# ProDoc_Schematic1.net
KiCad netlist of a schematic drawn in EasyEDA Pro
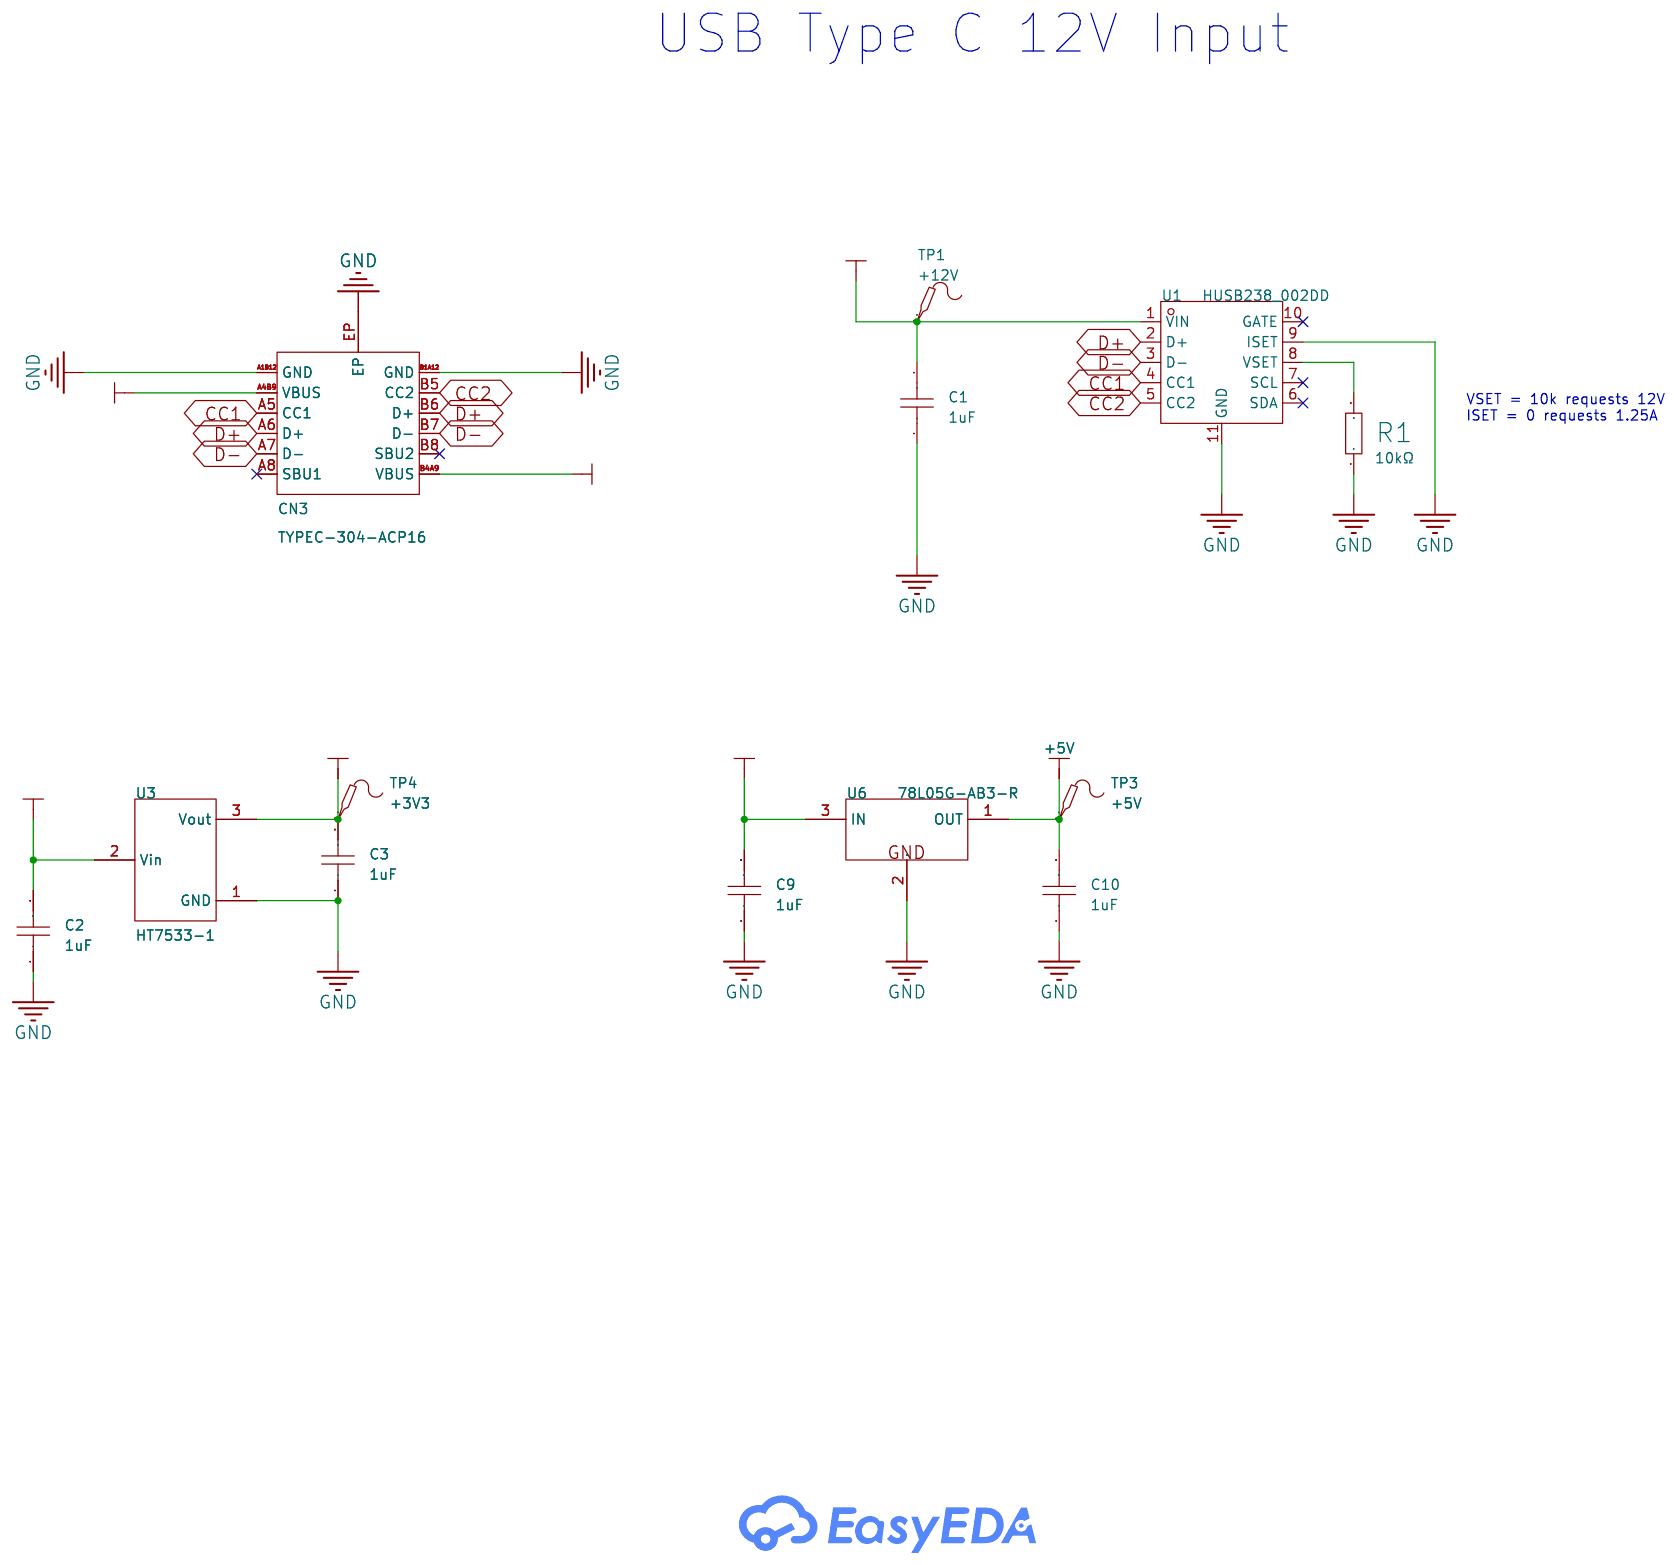
[diagram p0: P1]
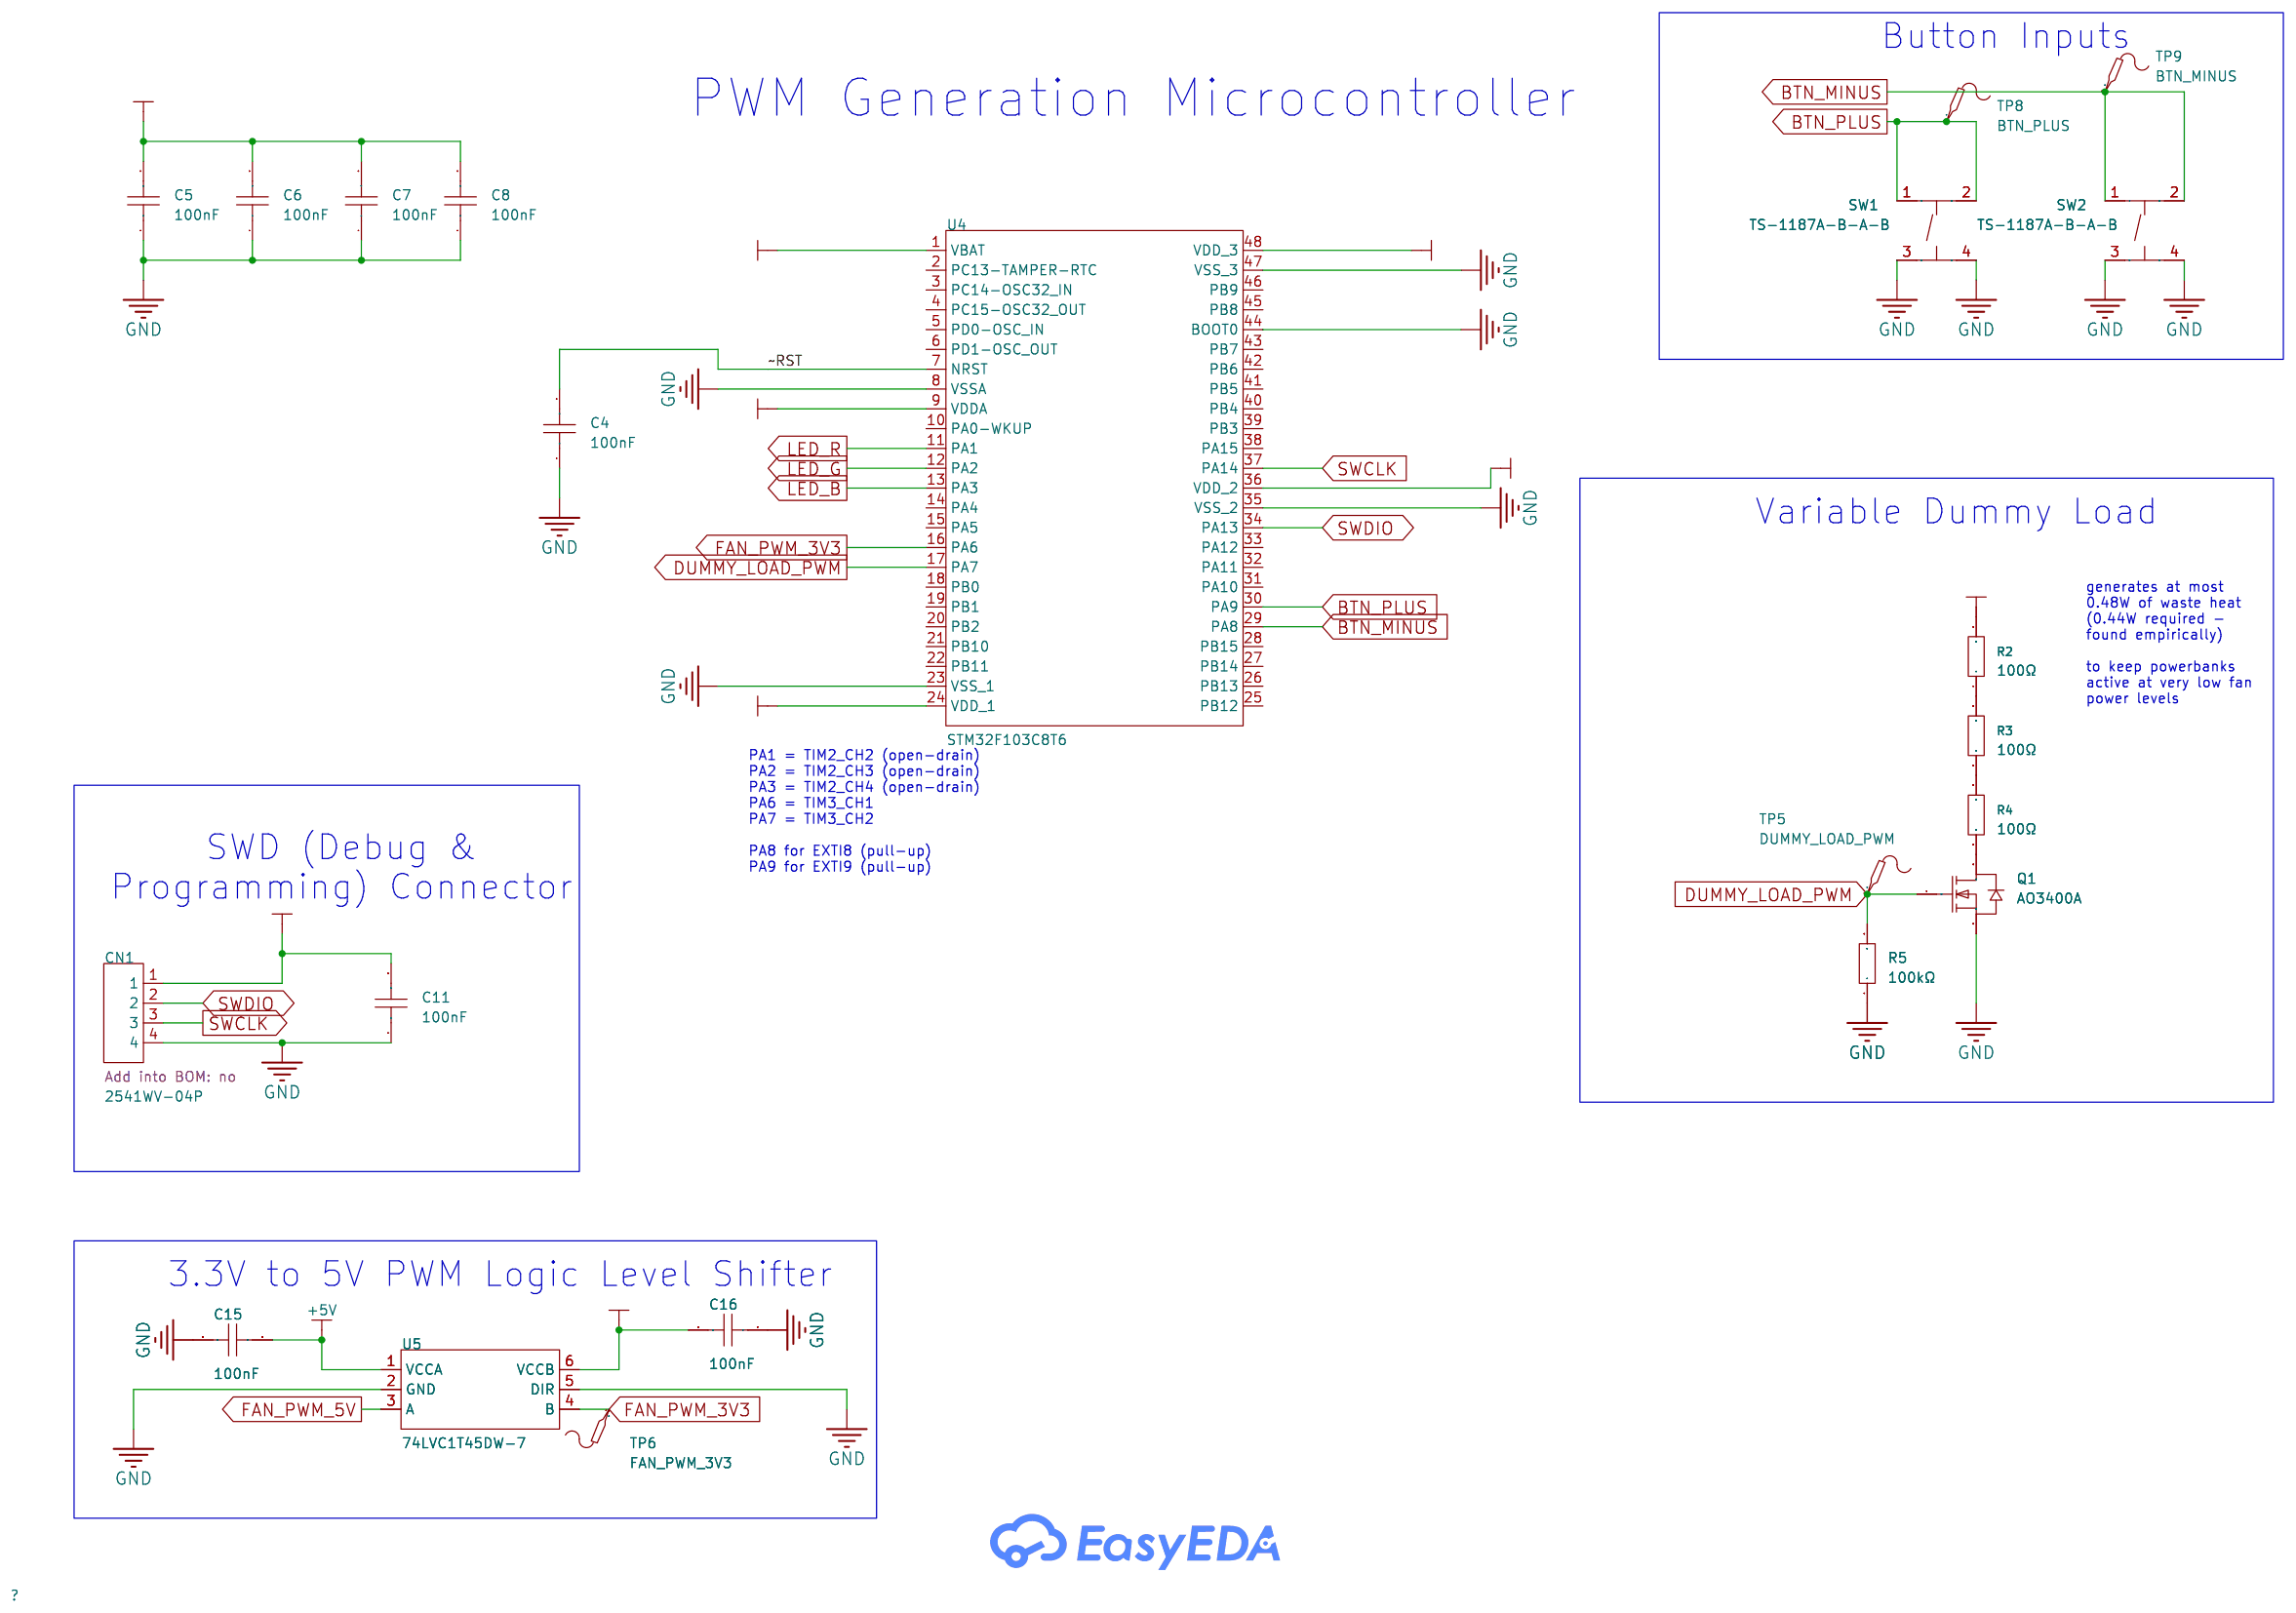
[diagram p1: P2]
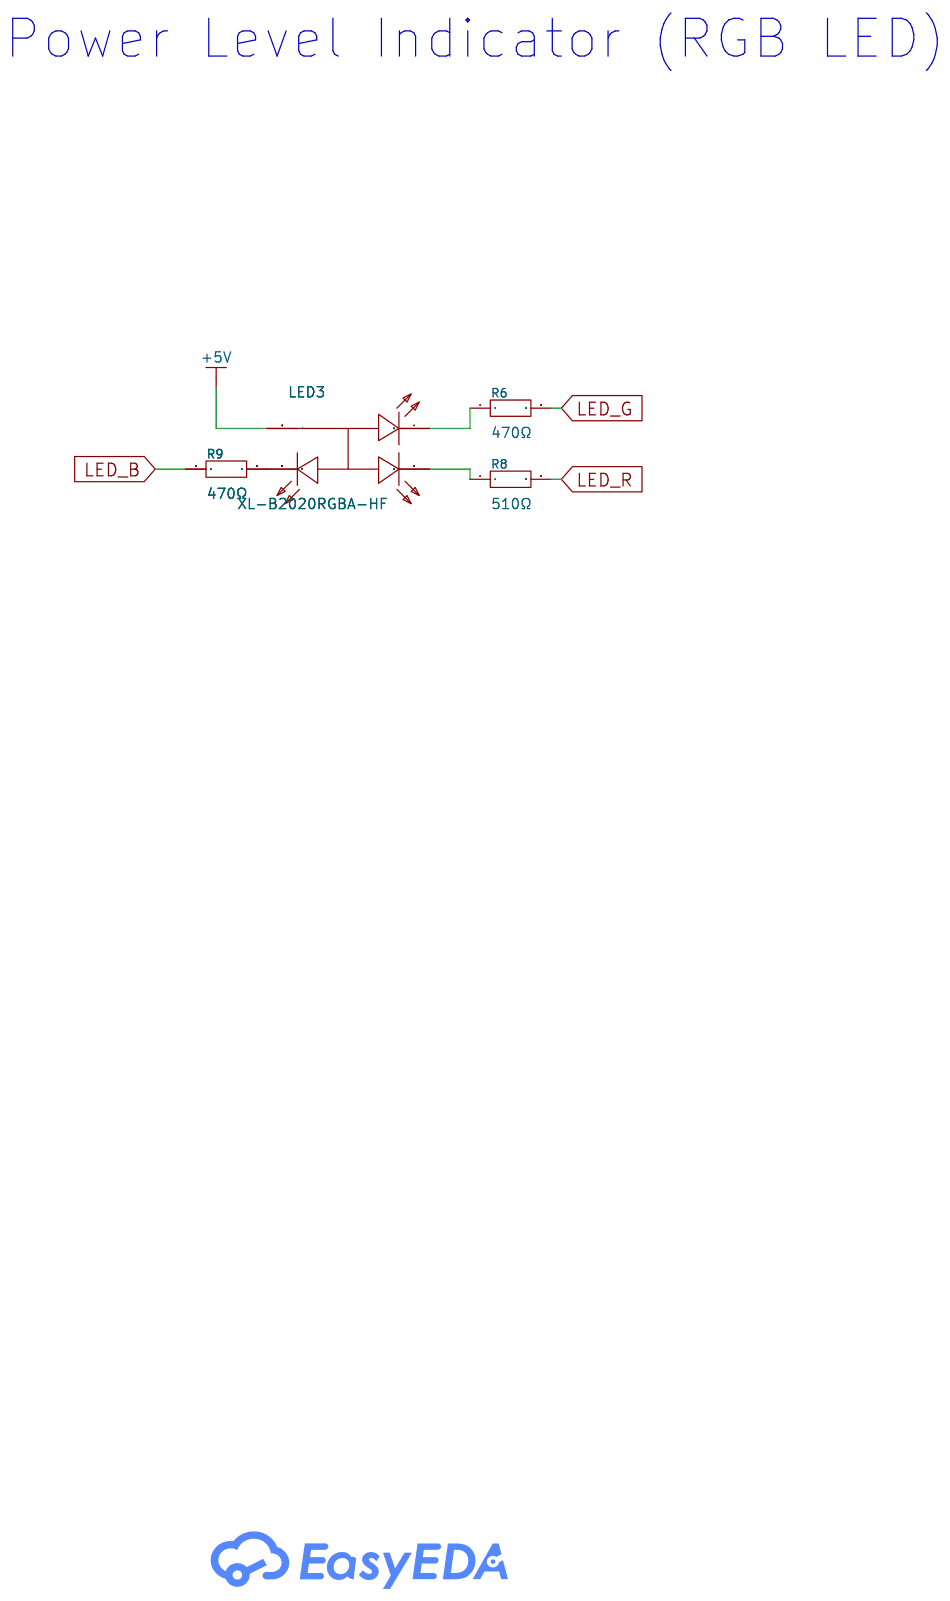
[diagram p2: P3]
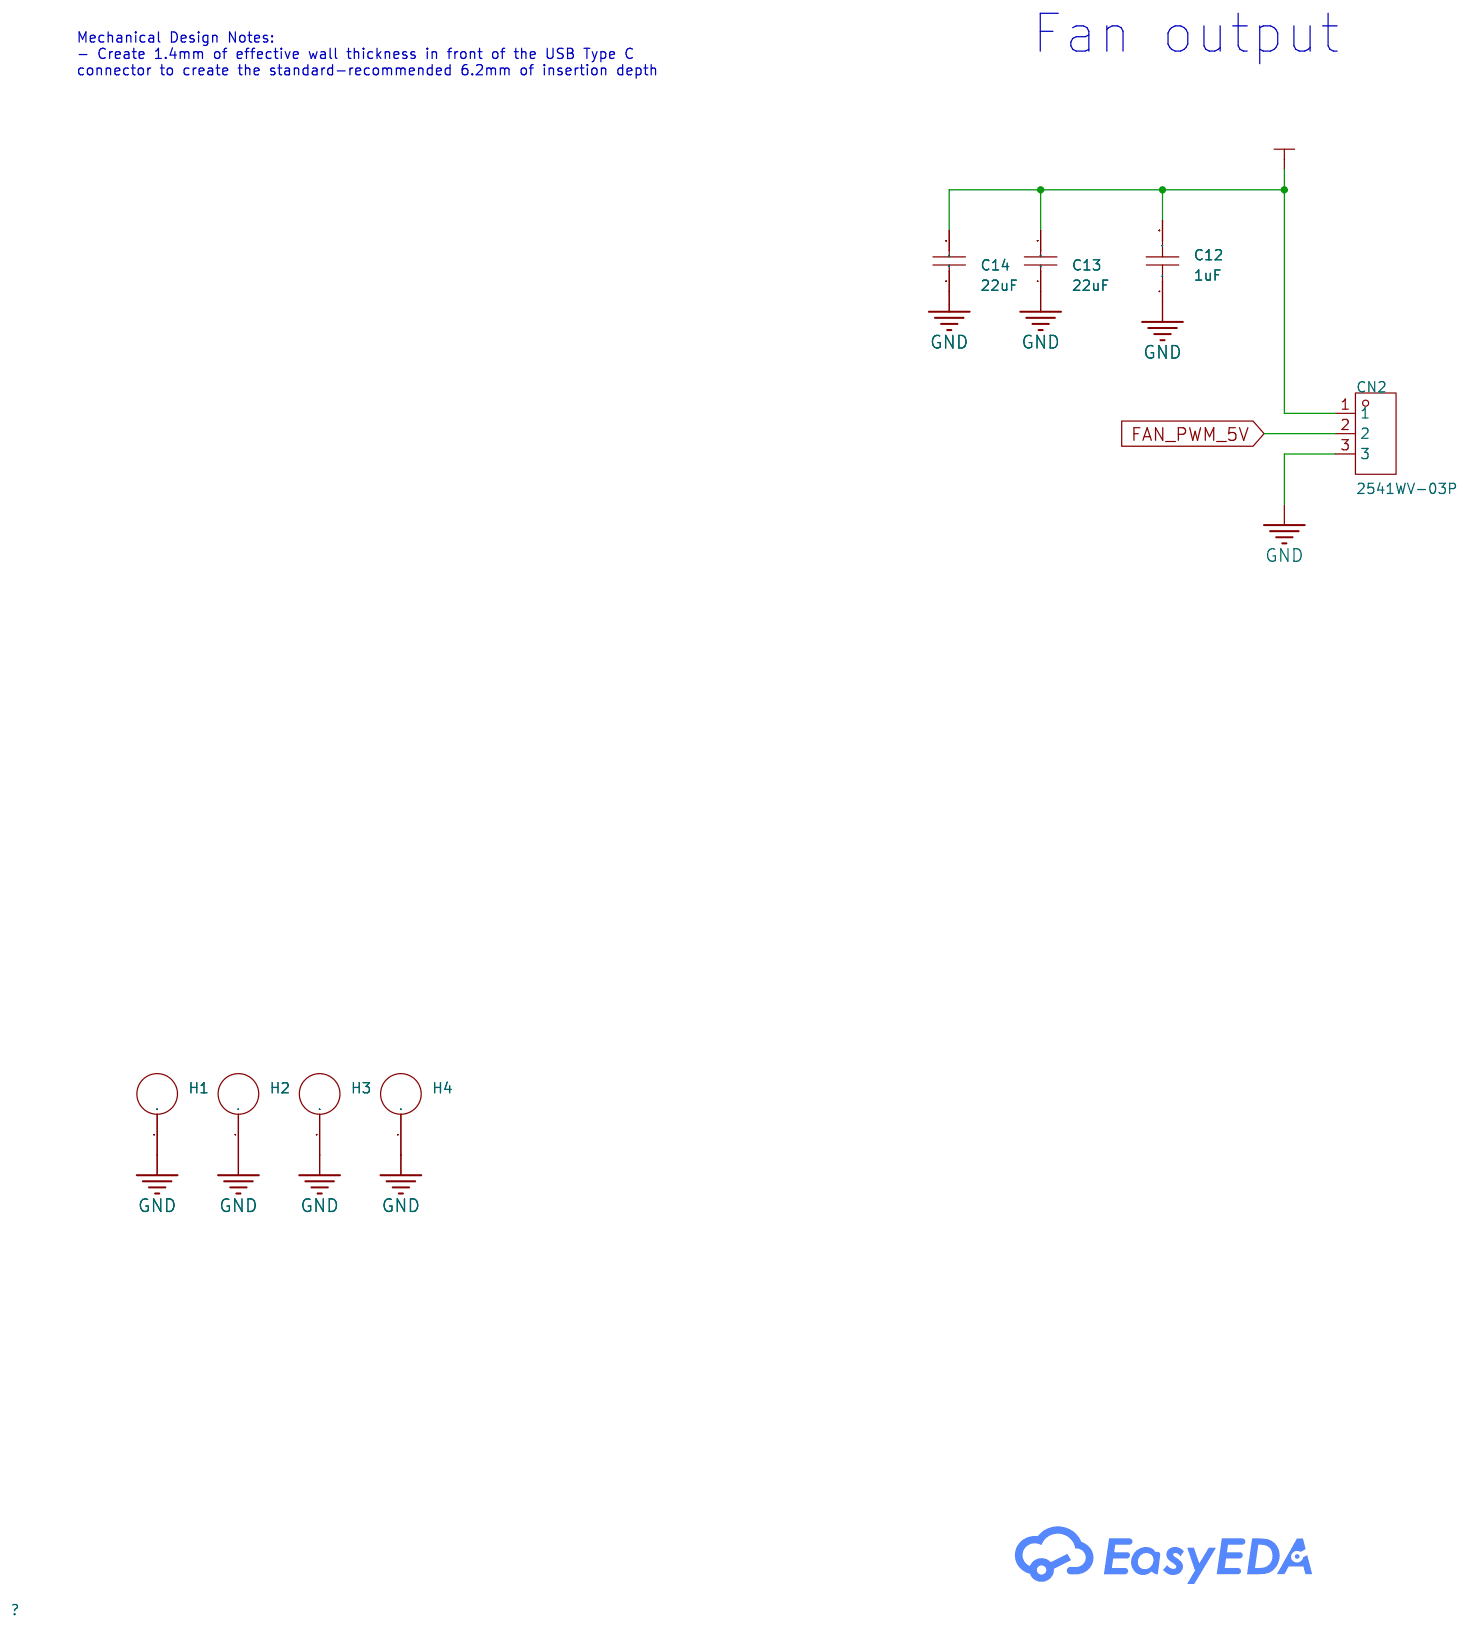
[diagram p3: P4]

(export (version "E")
  (design (tool "Eeschema 10.0.6"))
  (components
    (comp (ref "C1")
      (value "1uF")
      (footprint "easyedapro:C0603")
      (description "Capacitance:1uF Tolerance:±10% Tolerance:±10% Voltage Rating:50V Temperature Coefficient:X5R")
      (fields
        (field (name "Manufacturer Part") "CL10A105KB8NNNC")
        (field (name "Manufacturer") "SAMSUNG(三星)")
      )
      (libsource (lib "easyedapro") (part "CL10A105KB8NNNC"))
    )
    (comp (ref "C2")
      (value "1uF")
      (footprint "easyedapro:C0603")
      (description "Capacitance:1uF Tolerance:±10% Tolerance:±10% Voltage Rating:50V Temperature Coefficient:X5R")
      (fields
        (field (name "Manufacturer Part") "CL10A105KB8NNNC")
        (field (name "Manufacturer") "SAMSUNG(三星)")
      )
      (libsource (lib "easyedapro") (part "CL10A105KB8NNNC"))
    )
    (comp (ref "C3")
      (value "1uF")
      (footprint "easyedapro:C0603")
      (description "Capacitance:1uF Tolerance:±10% Tolerance:±10% Voltage Rating:50V Temperature Coefficient:X5R")
      (fields
        (field (name "Manufacturer Part") "CL10A105KB8NNNC")
        (field (name "Manufacturer") "SAMSUNG(三星)")
      )
      (libsource (lib "easyedapro") (part "CL10A105KB8NNNC"))
    )
    (comp (ref "C9")
      (value "1uF")
      (footprint "easyedapro:C0603")
      (description "Capacitance:1uF Tolerance:±10% Tolerance:±10% Voltage Rating:50V Temperature Coefficient:X5R")
      (fields
        (field (name "Manufacturer Part") "CL10A105KB8NNNC")
        (field (name "Manufacturer") "SAMSUNG(三星)")
      )
      (libsource (lib "easyedapro") (part "CL10A105KB8NNNC"))
    )
    (comp (ref "C10")
      (value "1uF")
      (footprint "easyedapro:C0603")
      (description "Capacitance:1uF Tolerance:±10% Tolerance:±10% Voltage Rating:50V Temperature Coefficient:X5R")
      (fields
        (field (name "Manufacturer Part") "CL10A105KB8NNNC")
        (field (name "Manufacturer") "SAMSUNG(三星)")
      )
      (libsource (lib "easyedapro") (part "CL10A105KB8NNNC"))
    )
    (comp (ref "CN3")
      (value "TYPEC-304-ACP16")
      (footprint "easyedapro:USB-C-SMD_TYPE-C-16P-1")
      (fields (field (name "Manufacturer") "XUNPU(讯普)"))
      (libsource (lib "easyedapro") (part "TYPEC-304-ACP16"))
    )
    (comp (ref "R1")
      (value "10kΩ")
      (footprint "easyedapro:R0603")
      (fields
        (field (name "Manufacturer Part") "0603WAF1002T5E")
        (field (name "Manufacturer") "UNI-ROYAL(厚声)")
      )
      (libsource (lib "easyedapro") (part "0603WAF1002T5E"))
    )
    (comp (ref "TP1")
      (value "+12V")
      (footprint "easyedapro:Test-Point-0.5mm")
      (description "Test Point 测试点")
      (libsource (lib "easyedapro") (part "Test-Point"))
    )
    (comp (ref "TP3")
      (value "+5V")
      (footprint "easyedapro:Test-Point-0.5mm")
      (description "Test Point 测试点")
      (libsource (lib "easyedapro") (part "Test-Point"))
    )
    (comp (ref "TP4")
      (value "+3V3")
      (footprint "easyedapro:Test-Point-0.5mm")
      (description "Test Point 测试点")
      (libsource (lib "easyedapro") (part "Test-Point"))
    )
    (comp (ref "U1")
      (value "HUSB238_002DD")
      (footprint "easyedapro:DFN-10_L3.0-W3.0-P0.50-BL-EP2.5")
      (fields (field (name "Manufacturer") "Hynetek(慧能泰)"))
      (libsource (lib "easyedapro") (part "HUSB238_002DD"))
    )
    (comp (ref "U3")
      (value "HT7533-1")
      (footprint "easyedapro:SOT-89-3_L4.5-W2.5-P1.50-LS4.2-BR")
      (fields (field (name "Manufacturer") "HOLTEK(合泰/盛群)"))
      (libsource (lib "easyedapro") (part "HT7533-1_C14289"))
    )
    (comp (ref "U6")
      (value "78L05G-AB3-R")
      (footprint "easyedapro:SOT-89-3_L4.5-W2.5-P1.50-LS4.2-BR")
      (fields (field (name "Manufacturer") "UTC(友顺)"))
      (libsource (lib "easyedapro") (part "78L05G-AB3-R"))
    )
    (comp (ref "C4")
      (value "100nF")
      (footprint "easyedapro:C0603")
      (description "Capacitance:100nF Tolerance:±10% Tolerance:±10% Voltage Rating:50V Temperature Coefficient:X7R")
      (fields
        (field (name "Manufacturer Part") "CC0603KRX7R9BB104")
        (field (name "Manufacturer") "YAGEO(国巨)")
      )
      (libsource (lib "easyedapro") (part "CC0603KRX7R9BB104"))
    )
    (comp (ref "C5")
      (value "100nF")
      (footprint "easyedapro:C0603")
      (description "Capacitance:100nF Tolerance:±10% Tolerance:±10% Voltage Rating:50V Temperature Coefficient:X7R")
      (fields
        (field (name "Manufacturer Part") "CC0603KRX7R9BB104")
        (field (name "Manufacturer") "YAGEO(国巨)")
      )
      (libsource (lib "easyedapro") (part "CC0603KRX7R9BB104"))
    )
    (comp (ref "C6")
      (value "100nF")
      (footprint "easyedapro:C0603")
      (description "Capacitance:100nF Tolerance:±10% Tolerance:±10% Voltage Rating:50V Temperature Coefficient:X7R")
      (fields
        (field (name "Manufacturer Part") "CC0603KRX7R9BB104")
        (field (name "Manufacturer") "YAGEO(国巨)")
      )
      (libsource (lib "easyedapro") (part "CC0603KRX7R9BB104"))
    )
    (comp (ref "C7")
      (value "100nF")
      (footprint "easyedapro:C0603")
      (description "Capacitance:100nF Tolerance:±10% Tolerance:±10% Voltage Rating:50V Temperature Coefficient:X7R")
      (fields
        (field (name "Manufacturer Part") "CC0603KRX7R9BB104")
        (field (name "Manufacturer") "YAGEO(国巨)")
      )
      (libsource (lib "easyedapro") (part "CC0603KRX7R9BB104"))
    )
    (comp (ref "C8")
      (value "100nF")
      (footprint "easyedapro:C0603")
      (description "Capacitance:100nF Tolerance:±10% Tolerance:±10% Voltage Rating:50V Temperature Coefficient:X7R")
      (fields
        (field (name "Manufacturer Part") "CC0603KRX7R9BB104")
        (field (name "Manufacturer") "YAGEO(国巨)")
      )
      (libsource (lib "easyedapro") (part "CC0603KRX7R9BB104"))
    )
    (comp (ref "C11")
      (value "100nF")
      (footprint "easyedapro:C0603")
      (description "Capacitance:100nF Tolerance:±10% Tolerance:±10% Voltage Rating:50V Temperature Coefficient:X7R")
      (fields
        (field (name "Manufacturer Part") "CC0603KRX7R9BB104")
        (field (name "Manufacturer") "YAGEO(国巨)")
      )
      (libsource (lib "easyedapro") (part "CC0603KRX7R9BB104"))
    )
    (comp (ref "C15")
      (value "100nF")
      (footprint "easyedapro:C0603")
      (description "Capacitance:100nF Tolerance:±10% Tolerance:±10% Voltage Rating:50V Temperature Coefficient:X7R")
      (fields
        (field (name "Manufacturer Part") "CC0603KRX7R9BB104")
        (field (name "Manufacturer") "YAGEO(国巨)")
      )
      (libsource (lib "easyedapro") (part "CC0603KRX7R9BB104"))
    )
    (comp (ref "C16")
      (value "100nF")
      (footprint "easyedapro:C0603")
      (description "Capacitance:100nF Tolerance:±10% Tolerance:±10% Voltage Rating:50V Temperature Coefficient:X7R")
      (fields
        (field (name "Manufacturer Part") "CC0603KRX7R9BB104")
        (field (name "Manufacturer") "YAGEO(国巨)")
      )
      (libsource (lib "easyedapro") (part "CC0603KRX7R9BB104"))
    )
    (comp (ref "CN1")
      (value "2541WV-04P")
      (footprint "easyedapro:HDR-TH_4P-P2.54-V-M-1")
      (fields (field (name "Manufacturer") "HanElectricity(瀚源)") (field (name "Add into BOM") "no"))
      (libsource (lib "easyedapro") (part "2541WV-04P"))
    )
    (comp (ref "Q1")
      (value "AO3400A")
      (footprint "easyedapro:SOT-23-3_L2.9-W1.3-P1.90-LS2.4-BR")
      (fields (field (name "Manufacturer") "AOS"))
      (libsource (lib "easyedapro") (part "AO3400A"))
    )
    (comp (ref "R2")
      (value "100Ω")
      (footprint "easyedapro:R1206")
      (fields
        (field (name "Manufacturer Part") "1206W4F1000T5E")
        (field (name "Manufacturer") "UNI-ROYAL(厚声)")
      )
      (libsource (lib "easyedapro") (part "1206W4F1000T5E"))
    )
    (comp (ref "R3")
      (value "100Ω")
      (footprint "easyedapro:R1206")
      (fields
        (field (name "Manufacturer Part") "1206W4F1000T5E")
        (field (name "Manufacturer") "UNI-ROYAL(厚声)")
      )
      (libsource (lib "easyedapro") (part "1206W4F1000T5E"))
    )
    (comp (ref "R4")
      (value "100Ω")
      (footprint "easyedapro:R1206")
      (fields
        (field (name "Manufacturer Part") "1206W4F1000T5E")
        (field (name "Manufacturer") "UNI-ROYAL(厚声)")
      )
      (libsource (lib "easyedapro") (part "1206W4F1000T5E"))
    )
    (comp (ref "R5")
      (value "100kΩ")
      (footprint "easyedapro:R0603")
      (fields
        (field (name "Manufacturer Part") "0603WAF1003T5E")
        (field (name "Manufacturer") "UNI-ROYAL(厚声)")
      )
      (libsource (lib "easyedapro") (part "0603WAF1003T5E"))
    )
    (comp (ref "SW1")
      (value "TS-1187A-B-A-B")
      (footprint "easyedapro:SW-SMD_4P-L5.1-W5.1-P3.70-LS6.5-TL_H1.5")
      (fields (field (name "Manufacturer") "XKB Connection(中国星坤)"))
      (libsource (lib "easyedapro") (part "TS-1187A-B-A-B"))
    )
    (comp (ref "SW2")
      (value "TS-1187A-B-A-B")
      (footprint "easyedapro:SW-SMD_4P-L5.1-W5.1-P3.70-LS6.5-TL_H1.5")
      (fields (field (name "Manufacturer") "XKB Connection(中国星坤)"))
      (libsource (lib "easyedapro") (part "TS-1187A-B-A-B"))
    )
    (comp (ref "TP5")
      (value "DUMMY_LOAD_PWM")
      (footprint "easyedapro:Test-Point-0.5mm")
      (description "Test Point 测试点")
      (libsource (lib "easyedapro") (part "Test-Point"))
    )
    (comp (ref "TP6")
      (value "FAN_PWM_3V3")
      (footprint "easyedapro:Test-Point-0.5mm")
      (description "Test Point 测试点")
      (libsource (lib "easyedapro") (part "Test-Point"))
    )
    (comp (ref "TP8")
      (value "BTN_PLUS")
      (footprint "easyedapro:Test-Point-0.5mm")
      (description "Test Point 测试点")
      (libsource (lib "easyedapro") (part "Test-Point"))
    )
    (comp (ref "TP9")
      (value "BTN_MINUS")
      (footprint "easyedapro:Test-Point-0.5mm")
      (description "Test Point 测试点")
      (libsource (lib "easyedapro") (part "Test-Point"))
    )
    (comp (ref "U4")
      (value "STM32F103C8T6")
      (footprint "easyedapro:LQFP-48_L7.0-W7.0-P0.50-LS9.0-BL")
      (fields (field (name "Manufacturer") "ST(意法半导体)"))
      (libsource (lib "easyedapro") (part "STM32F103C8T6"))
    )
    (comp (ref "U5")
      (value "74LVC1T45DW-7")
      (footprint "easyedapro:SC-70-6_L2.2-W1.3-P0.65-LS2.1-BR")
      (fields (field (name "Manufacturer") "DIODES(美台)"))
      (libsource (lib "easyedapro") (part "74LVC1T45DW-7"))
    )
    (comp (ref "LED3")
      (value "XL-B2020RGBA-HF")
      (footprint "easyedapro:LED-SMD_4P-L2.1-W2.1-P1.0-BL")
      (fields (field (name "Manufacturer") "XINGLIGHT(成兴光)"))
      (libsource (lib "easyedapro") (part "XL-B2020RGBA-HF"))
    )
    (comp (ref "R6")
      (value "470Ω")
      (footprint "easyedapro:R0402")
      (fields
        (field (name "Manufacturer Part") "0402WGF4700TCE")
        (field (name "Manufacturer") "UNI-ROYAL(厚声)")
      )
      (libsource (lib "easyedapro") (part "0402WGF4700TCE"))
    )
    (comp (ref "R8")
      (value "510Ω")
      (footprint "easyedapro:R0402")
      (fields
        (field (name "Manufacturer Part") "0402WGF5100TCE")
        (field (name "Manufacturer") "UNI-ROYAL(厚声)")
      )
      (libsource (lib "easyedapro") (part "0402WGF5100TCE"))
    )
    (comp (ref "R9")
      (value "470Ω")
      (footprint "easyedapro:R0402")
      (fields
        (field (name "Manufacturer Part") "0402WGF4700TCE")
        (field (name "Manufacturer") "UNI-ROYAL(厚声)")
      )
      (libsource (lib "easyedapro") (part "0402WGF4700TCE"))
    )
    (comp (ref "C12")
      (value "1uF")
      (footprint "easyedapro:C0603")
      (description "Capacitance:1uF Tolerance:±10% Tolerance:±10% Voltage Rating:50V Temperature Coefficient:X5R")
      (fields
        (field (name "Manufacturer Part") "CL10A105KB8NNNC")
        (field (name "Manufacturer") "SAMSUNG(三星)")
      )
      (libsource (lib "easyedapro") (part "CL10A105KB8NNNC"))
    )
    (comp (ref "C13")
      (value "22uF")
      (footprint "easyedapro:C1206")
      (description "Capacitance:22uF Tolerance:±10% Tolerance:±10% Voltage Rating:25V Temperature Coefficient:X5R")
      (fields
        (field (name "Manufacturer Part") "CL31A226KAHNNNE")
        (field (name "Manufacturer") "SAMSUNG(三星)")
      )
      (libsource (lib "easyedapro") (part "CL31A226KAHNNNE"))
    )
    (comp (ref "C14")
      (value "22uF")
      (footprint "easyedapro:C1206")
      (description "Capacitance:22uF Tolerance:±10% Tolerance:±10% Voltage Rating:25V Temperature Coefficient:X5R")
      (fields
        (field (name "Manufacturer Part") "CL31A226KAHNNNE")
        (field (name "Manufacturer") "SAMSUNG(三星)")
      )
      (libsource (lib "easyedapro") (part "CL31A226KAHNNNE"))
    )
    (comp (ref "CN2")
      (value "2541WV-03P")
      (footprint "easyedapro:HDR-TH_3P-P2.54-V-M-2")
      (fields (field (name "Manufacturer") "HanElectricity(瀚源)"))
      (libsource (lib "easyedapro") (part "2541WV-03P"))
    )
    (comp (ref "H1")
      (value "~")
      (footprint "easyedapro:HOLE_D2M5_D4M0_PAD_PTH")
      (libsource (lib "easyedapro") (part "HOLE_D2M5_D4M0_PAD_PTH"))
    )
    (comp (ref "H2")
      (value "~")
      (footprint "easyedapro:HOLE_D2M5_D4M0_PAD_PTH")
      (libsource (lib "easyedapro") (part "HOLE_D2M5_D4M0_PAD_PTH"))
    )
    (comp (ref "H3")
      (value "~")
      (footprint "easyedapro:HOLE_D2M5_D4M0_PAD_PTH")
      (libsource (lib "easyedapro") (part "HOLE_D2M5_D4M0_PAD_PTH"))
    )
    (comp (ref "H4")
      (value "~")
      (footprint "easyedapro:HOLE_D2M5_D4M0_PAD_PTH")
      (libsource (lib "easyedapro") (part "HOLE_D2M5_D4M0_PAD_PTH"))
    )
  )
  (nets
    (net (code "1") (name "+3V3") (class "Default")
      (node (ref "C11") (pin "2") (pinfunction "2_2") (pintype "unspecified"))
      (node (ref "C16") (pin "2") (pinfunction "2_2") (pintype "unspecified"))
      (node (ref "C3") (pin "2") (pinfunction "2_2") (pintype "unspecified"))
      (node (ref "C5") (pin "2") (pinfunction "2_2") (pintype "unspecified"))
      (node (ref "C6") (pin "2") (pinfunction "2_2") (pintype "unspecified"))
      (node (ref "C7") (pin "2") (pinfunction "2_2") (pintype "unspecified"))
      (node (ref "C8") (pin "2") (pinfunction "2_2") (pintype "unspecified"))
      (node (ref "CN1") (pin "1") (pinfunction "1_1") (pintype "unspecified"))
      (node (ref "TP4") (pin "1") (pinfunction "1_1") (pintype "unspecified"))
      (node (ref "U3") (pin "3") (pinfunction "Vout_3") (pintype "unspecified"))
      (node (ref "U4") (pin "1") (pinfunction "VBAT_1") (pintype "unspecified"))
      (node (ref "U4") (pin "24") (pinfunction "VDD_1_24") (pintype "unspecified"))
      (node (ref "U4") (pin "36") (pinfunction "VDD_2_36") (pintype "unspecified"))
      (node (ref "U4") (pin "48") (pinfunction "VDD_3_48") (pintype "unspecified"))
      (node (ref "U4") (pin "9") (pinfunction "VDDA_9") (pintype "unspecified"))
      (node (ref "U5") (pin "6") (pinfunction "VCCB_6") (pintype "unspecified"))
    )
    (net (code "2") (name "+5V") (class "Default")
      (node (ref "C10") (pin "2") (pinfunction "2_2") (pintype "unspecified"))
      (node (ref "C15") (pin "1") (pinfunction "1_1") (pintype "unspecified"))
      (node (ref "LED3") (pin "3") (pinfunction "A_3") (pintype "unspecified"))
      (node (ref "TP3") (pin "1") (pinfunction "1_1") (pintype "unspecified"))
      (node (ref "U5") (pin "1") (pinfunction "VCCA_1") (pintype "unspecified"))
      (node (ref "U6") (pin "1") (pinfunction "OUT_1") (pintype "unspecified"))
    )
    (net (code "3") (name "+12V") (class "Default")
      (node (ref "C1") (pin "2") (pinfunction "2_2") (pintype "unspecified"))
      (node (ref "C12") (pin "2") (pinfunction "2_2") (pintype "unspecified"))
      (node (ref "C13") (pin "2") (pinfunction "2_2") (pintype "input"))
      (node (ref "C14") (pin "2") (pinfunction "2_2") (pintype "input"))
      (node (ref "C2") (pin "2") (pinfunction "2_2") (pintype "unspecified"))
      (node (ref "C9") (pin "2") (pinfunction "2_2") (pintype "unspecified"))
      (node (ref "CN2") (pin "1") (pinfunction "1_1") (pintype "unspecified"))
      (node (ref "CN3") (pin "A4B9") (pinfunction "VBUS_A4B9") (pintype "unspecified"))
      (node (ref "CN3") (pin "B4A9") (pinfunction "VBUS_B4A9") (pintype "unspecified"))
      (node (ref "R2") (pin "2") (pinfunction "2_2") (pintype "input"))
      (node (ref "TP1") (pin "1") (pinfunction "1_1") (pintype "unspecified"))
      (node (ref "U1") (pin "1") (pinfunction "VIN_1") (pintype "unspecified"))
      (node (ref "U3") (pin "2") (pinfunction "Vin_2") (pintype "unspecified"))
      (node (ref "U6") (pin "3") (pinfunction "IN_3") (pintype "unspecified"))
    )
    (net (code "4") (name "BTN_MINUS") (class "Default")
      (node (ref "SW2") (pin "1") (pinfunction "A_1") (pintype "unspecified"))
      (node (ref "SW2") (pin "2") (pinfunction "B_2") (pintype "unspecified"))
      (node (ref "TP9") (pin "1") (pinfunction "1_1") (pintype "unspecified"))
      (node (ref "U4") (pin "29") (pinfunction "PA8_29") (pintype "unspecified"))
    )
    (net (code "5") (name "BTN_PLUS") (class "Default")
      (node (ref "SW1") (pin "1") (pinfunction "A_1") (pintype "unspecified"))
      (node (ref "SW1") (pin "2") (pinfunction "B_2") (pintype "unspecified"))
      (node (ref "TP8") (pin "1") (pinfunction "1_1") (pintype "unspecified"))
      (node (ref "U4") (pin "30") (pinfunction "PA9_30") (pintype "unspecified"))
    )
    (net (code "6") (name "CC1") (class "Default")
      (node (ref "CN3") (pin "A5") (pinfunction "CC1_A5") (pintype "unspecified"))
      (node (ref "U1") (pin "4") (pinfunction "CC1_4") (pintype "unspecified"))
    )
    (net (code "7") (name "CC2") (class "Default")
      (node (ref "CN3") (pin "B5") (pinfunction "CC2_B5") (pintype "unspecified"))
      (node (ref "U1") (pin "5") (pinfunction "CC2_5") (pintype "unspecified"))
    )
    (net (code "8") (name "D+") (class "Default")
      (node (ref "CN3") (pin "A6") (pinfunction "D+_A6") (pintype "unspecified"))
      (node (ref "CN3") (pin "B6") (pinfunction "D+_B6") (pintype "unspecified"))
      (node (ref "U1") (pin "2") (pinfunction "D+_2") (pintype "unspecified"))
    )
    (net (code "9") (name "D-") (class "Default")
      (node (ref "CN3") (pin "A7") (pinfunction "D-_A7") (pintype "unspecified"))
      (node (ref "CN3") (pin "B7") (pinfunction "D-_B7") (pintype "unspecified"))
      (node (ref "U1") (pin "3") (pinfunction "D-_3") (pintype "unspecified"))
    )
    (net (code "10") (name "DUMMY_LOAD_PWM") (class "Default")
      (node (ref "Q1") (pin "1") (pinfunction "G_1") (pintype "unspecified"))
      (node (ref "R5") (pin "2") (pinfunction "2_2") (pintype "input"))
      (node (ref "TP5") (pin "1") (pinfunction "1_1") (pintype "unspecified"))
      (node (ref "U4") (pin "17") (pinfunction "PA7_17") (pintype "unspecified"))
    )
    (net (code "11") (name "FAN_PWM_3V3") (class "Default")
      (node (ref "TP6") (pin "1") (pinfunction "1_1") (pintype "unspecified"))
      (node (ref "U4") (pin "16") (pinfunction "PA6_16") (pintype "unspecified"))
      (node (ref "U5") (pin "4") (pinfunction "B_4") (pintype "unspecified"))
    )
    (net (code "12") (name "FAN_PWM_5V") (class "Default")
      (node (ref "CN2") (pin "2") (pinfunction "2_2") (pintype "unspecified"))
      (node (ref "U5") (pin "3") (pinfunction "A_3") (pintype "unspecified"))
    )
    (net (code "13") (name "GND") (class "Default")
      (node (ref "C1") (pin "1") (pinfunction "1_1") (pintype "unspecified"))
      (node (ref "C10") (pin "1") (pinfunction "1_1") (pintype "unspecified"))
      (node (ref "C11") (pin "1") (pinfunction "1_1") (pintype "unspecified"))
      (node (ref "C12") (pin "1") (pinfunction "1_1") (pintype "unspecified"))
      (node (ref "C13") (pin "1") (pinfunction "1_1") (pintype "input"))
      (node (ref "C14") (pin "1") (pinfunction "1_1") (pintype "input"))
      (node (ref "C15") (pin "2") (pinfunction "2_2") (pintype "unspecified"))
      (node (ref "C16") (pin "1") (pinfunction "1_1") (pintype "unspecified"))
      (node (ref "C2") (pin "1") (pinfunction "1_1") (pintype "unspecified"))
      (node (ref "C3") (pin "1") (pinfunction "1_1") (pintype "unspecified"))
      (node (ref "C4") (pin "1") (pinfunction "1_1") (pintype "unspecified"))
      (node (ref "C5") (pin "1") (pinfunction "1_1") (pintype "unspecified"))
      (node (ref "C6") (pin "1") (pinfunction "1_1") (pintype "unspecified"))
      (node (ref "C7") (pin "1") (pinfunction "1_1") (pintype "unspecified"))
      (node (ref "C8") (pin "1") (pinfunction "1_1") (pintype "unspecified"))
      (node (ref "C9") (pin "1") (pinfunction "1_1") (pintype "unspecified"))
      (node (ref "CN1") (pin "4") (pinfunction "4_4") (pintype "unspecified"))
      (node (ref "CN2") (pin "3") (pinfunction "3_3") (pintype "unspecified"))
      (node (ref "CN3") (pin "A1B12") (pinfunction "GND_A1B12") (pintype "unspecified"))
      (node (ref "CN3") (pin "B1A12") (pinfunction "GND_B1A12") (pintype "unspecified"))
      (node (ref "CN3") (pin "EP") (pinfunction "EP_EP") (pintype "unspecified"))
      (node (ref "H1") (pin "1") (pinfunction "1_1") (pintype "input"))
      (node (ref "H2") (pin "1") (pinfunction "1_1") (pintype "input"))
      (node (ref "H3") (pin "1") (pinfunction "1_1") (pintype "input"))
      (node (ref "H4") (pin "1") (pinfunction "1_1") (pintype "input"))
      (node (ref "Q1") (pin "2") (pinfunction "S_2") (pintype "unspecified"))
      (node (ref "R1") (pin "1") (pinfunction "1_1") (pintype "input"))
      (node (ref "R5") (pin "1") (pinfunction "1_1") (pintype "input"))
      (node (ref "SW1") (pin "3") (pinfunction "C_3") (pintype "unspecified"))
      (node (ref "SW1") (pin "4") (pinfunction "D_4") (pintype "unspecified"))
      (node (ref "SW2") (pin "3") (pinfunction "C_3") (pintype "unspecified"))
      (node (ref "SW2") (pin "4") (pinfunction "D_4") (pintype "unspecified"))
      (node (ref "U1") (pin "11") (pinfunction "GND_11") (pintype "unspecified"))
      (node (ref "U1") (pin "9") (pinfunction "ISET_9") (pintype "unspecified"))
      (node (ref "U3") (pin "1") (pinfunction "GND_1") (pintype "unspecified"))
      (node (ref "U4") (pin "23") (pinfunction "VSS_1_23") (pintype "unspecified"))
      (node (ref "U4") (pin "35") (pinfunction "VSS_2_35") (pintype "unspecified"))
      (node (ref "U4") (pin "44") (pinfunction "BOOT0_44") (pintype "unspecified"))
      (node (ref "U4") (pin "47") (pinfunction "VSS_3_47") (pintype "unspecified"))
      (node (ref "U4") (pin "8") (pinfunction "VSSA_8") (pintype "unspecified"))
      (node (ref "U5") (pin "2") (pinfunction "GND_2") (pintype "unspecified"))
      (node (ref "U5") (pin "5") (pinfunction "DIR_5") (pintype "unspecified"))
      (node (ref "U6") (pin "2") (pinfunction "GND_2") (pintype "unspecified"))
    )
    (net (code "14") (name "LED_B") (class "Default")
      (node (ref "R9") (pin "1") (pinfunction "1_1") (pintype "input"))
      (node (ref "U4") (pin "13") (pinfunction "PA3_13") (pintype "unspecified"))
    )
    (net (code "15") (name "LED_G") (class "Default")
      (node (ref "R6") (pin "2") (pinfunction "2_2") (pintype "input"))
      (node (ref "U4") (pin "12") (pinfunction "PA2_12") (pintype "unspecified"))
    )
    (net (code "16") (name "LED_R") (class "Default")
      (node (ref "R8") (pin "2") (pinfunction "2_2") (pintype "input"))
      (node (ref "U4") (pin "11") (pinfunction "PA1_11") (pintype "unspecified"))
    )
    (net (code "17") (name "Net-(LED3-C-Pad1)") (class "Default")
      (node (ref "LED3") (pin "1") (pinfunction "C_1") (pintype "unspecified"))
      (node (ref "R8") (pin "1") (pinfunction "1_1") (pintype "input"))
    )
    (net (code "18") (name "Net-(LED3-C-Pad2)") (class "Default")
      (node (ref "LED3") (pin "2") (pinfunction "C_2") (pintype "unspecified"))
      (node (ref "R9") (pin "2") (pinfunction "2_2") (pintype "input"))
    )
    (net (code "19") (name "Net-(LED3-C-Pad4)") (class "Default")
      (node (ref "LED3") (pin "4") (pinfunction "C_4") (pintype "unspecified"))
      (node (ref "R6") (pin "1") (pinfunction "1_1") (pintype "input"))
    )
    (net (code "20") (name "Net-(Q1-D)") (class "Default")
      (node (ref "Q1") (pin "3") (pinfunction "D_3") (pintype "unspecified"))
      (node (ref "R4") (pin "1") (pinfunction "1_1") (pintype "input"))
    )
    (net (code "21") (name "Net-(R2-Pad1)") (class "Default")
      (node (ref "R2") (pin "1") (pinfunction "1_1") (pintype "input"))
      (node (ref "R3") (pin "2") (pinfunction "2_2") (pintype "input"))
    )
    (net (code "22") (name "Net-(R3-Pad1)") (class "Default")
      (node (ref "R3") (pin "1") (pinfunction "1_1") (pintype "input"))
      (node (ref "R4") (pin "2") (pinfunction "2_2") (pintype "input"))
    )
    (net (code "23") (name "Net-(U1-VSET)") (class "Default")
      (node (ref "R1") (pin "2") (pinfunction "2_2") (pintype "input"))
      (node (ref "U1") (pin "8") (pinfunction "VSET_8") (pintype "unspecified"))
    )
    (net (code "24") (name "SWCLK") (class "Default")
      (node (ref "CN1") (pin "3") (pinfunction "3_3") (pintype "unspecified"))
      (node (ref "U4") (pin "37") (pinfunction "PA14_37") (pintype "unspecified"))
    )
    (net (code "25") (name "SWDIO") (class "Default")
      (node (ref "CN1") (pin "2") (pinfunction "2_2") (pintype "unspecified"))
      (node (ref "U4") (pin "34") (pinfunction "PA13_34") (pintype "unspecified"))
    )
    (net (code "26") (name "unconnected-(CN3-SBU1-PadA8)") (class "Default")
      (node (ref "CN3") (pin "A8") (pinfunction "SBU1_A8") (pintype "unspecified+no_connect"))
    )
    (net (code "27") (name "unconnected-(CN3-SBU2-PadB8)") (class "Default")
      (node (ref "CN3") (pin "B8") (pinfunction "SBU2_B8") (pintype "unspecified+no_connect"))
    )
    (net (code "28") (name "unconnected-(U1-GATE-Pad10)") (class "Default")
      (node (ref "U1") (pin "10") (pinfunction "GATE_10") (pintype "unspecified+no_connect"))
    )
    (net (code "29") (name "unconnected-(U1-SCL-Pad7)") (class "Default")
      (node (ref "U1") (pin "7") (pinfunction "SCL_7") (pintype "unspecified+no_connect"))
    )
    (net (code "30") (name "unconnected-(U1-SDA-Pad6)") (class "Default")
      (node (ref "U1") (pin "6") (pinfunction "SDA_6") (pintype "unspecified+no_connect"))
    )
    (net (code "31") (name "unconnected-(U4-PA0-WKUP-Pad10)") (class "Default")
      (node (ref "U4") (pin "10") (pinfunction "PA0-WKUP_10") (pintype "unspecified"))
    )
    (net (code "32") (name "unconnected-(U4-PA4-Pad14)") (class "Default")
      (node (ref "U4") (pin "14") (pinfunction "PA4_14") (pintype "unspecified"))
    )
    (net (code "33") (name "unconnected-(U4-PA5-Pad15)") (class "Default")
      (node (ref "U4") (pin "15") (pinfunction "PA5_15") (pintype "unspecified"))
    )
    (net (code "34") (name "unconnected-(U4-PA10-Pad31)") (class "Default")
      (node (ref "U4") (pin "31") (pinfunction "PA10_31") (pintype "unspecified"))
    )
    (net (code "35") (name "unconnected-(U4-PA11-Pad32)") (class "Default")
      (node (ref "U4") (pin "32") (pinfunction "PA11_32") (pintype "unspecified"))
    )
    (net (code "36") (name "unconnected-(U4-PA12-Pad33)") (class "Default")
      (node (ref "U4") (pin "33") (pinfunction "PA12_33") (pintype "unspecified"))
    )
    (net (code "37") (name "unconnected-(U4-PA15-Pad38)") (class "Default")
      (node (ref "U4") (pin "38") (pinfunction "PA15_38") (pintype "unspecified"))
    )
    (net (code "38") (name "unconnected-(U4-PB0-Pad18)") (class "Default")
      (node (ref "U4") (pin "18") (pinfunction "PB0_18") (pintype "unspecified"))
    )
    (net (code "39") (name "unconnected-(U4-PB1-Pad19)") (class "Default")
      (node (ref "U4") (pin "19") (pinfunction "PB1_19") (pintype "unspecified"))
    )
    (net (code "40") (name "unconnected-(U4-PB2-Pad20)") (class "Default")
      (node (ref "U4") (pin "20") (pinfunction "PB2_20") (pintype "unspecified"))
    )
    (net (code "41") (name "unconnected-(U4-PB3-Pad39)") (class "Default")
      (node (ref "U4") (pin "39") (pinfunction "PB3_39") (pintype "unspecified"))
    )
    (net (code "42") (name "unconnected-(U4-PB4-Pad40)") (class "Default")
      (node (ref "U4") (pin "40") (pinfunction "PB4_40") (pintype "unspecified"))
    )
    (net (code "43") (name "unconnected-(U4-PB5-Pad41)") (class "Default")
      (node (ref "U4") (pin "41") (pinfunction "PB5_41") (pintype "unspecified"))
    )
    (net (code "44") (name "unconnected-(U4-PB6-Pad42)") (class "Default")
      (node (ref "U4") (pin "42") (pinfunction "PB6_42") (pintype "unspecified"))
    )
    (net (code "45") (name "unconnected-(U4-PB7-Pad43)") (class "Default")
      (node (ref "U4") (pin "43") (pinfunction "PB7_43") (pintype "unspecified"))
    )
    (net (code "46") (name "unconnected-(U4-PB8-Pad45)") (class "Default")
      (node (ref "U4") (pin "45") (pinfunction "PB8_45") (pintype "unspecified"))
    )
    (net (code "47") (name "unconnected-(U4-PB9-Pad46)") (class "Default")
      (node (ref "U4") (pin "46") (pinfunction "PB9_46") (pintype "unspecified"))
    )
    (net (code "48") (name "unconnected-(U4-PB10-Pad21)") (class "Default")
      (node (ref "U4") (pin "21") (pinfunction "PB10_21") (pintype "unspecified"))
    )
    (net (code "49") (name "unconnected-(U4-PB11-Pad22)") (class "Default")
      (node (ref "U4") (pin "22") (pinfunction "PB11_22") (pintype "unspecified"))
    )
    (net (code "50") (name "unconnected-(U4-PB12-Pad25)") (class "Default")
      (node (ref "U4") (pin "25") (pinfunction "PB12_25") (pintype "unspecified"))
    )
    (net (code "51") (name "unconnected-(U4-PB13-Pad26)") (class "Default")
      (node (ref "U4") (pin "26") (pinfunction "PB13_26") (pintype "unspecified"))
    )
    (net (code "52") (name "unconnected-(U4-PB14-Pad27)") (class "Default")
      (node (ref "U4") (pin "27") (pinfunction "PB14_27") (pintype "unspecified"))
    )
    (net (code "53") (name "unconnected-(U4-PB15-Pad28)") (class "Default")
      (node (ref "U4") (pin "28") (pinfunction "PB15_28") (pintype "unspecified"))
    )
    (net (code "54") (name "unconnected-(U4-PC13-TAMPER-RTC-Pad2)") (class "Default")
      (node (ref "U4") (pin "2") (pinfunction "PC13-TAMPER-RTC_2") (pintype "unspecified"))
    )
    (net (code "55") (name "unconnected-(U4-PC14-OSC32_IN-Pad3)") (class "Default")
      (node (ref "U4") (pin "3") (pinfunction "PC14-OSC32_IN_3") (pintype "unspecified"))
    )
    (net (code "56") (name "unconnected-(U4-PC15-OSC32_OUT-Pad4)") (class "Default")
      (node (ref "U4") (pin "4") (pinfunction "PC15-OSC32_OUT_4") (pintype "unspecified"))
    )
    (net (code "57") (name "unconnected-(U4-PD0-OSC_IN-Pad5)") (class "Default")
      (node (ref "U4") (pin "5") (pinfunction "PD0-OSC_IN_5") (pintype "unspecified"))
    )
    (net (code "58") (name "unconnected-(U4-PD1-OSC_OUT-Pad6)") (class "Default")
      (node (ref "U4") (pin "6") (pinfunction "PD1-OSC_OUT_6") (pintype "unspecified"))
    )
    (net (code "59") (name "~RST") (class "Default")
      (node (ref "C4") (pin "2") (pinfunction "2_2") (pintype "unspecified"))
      (node (ref "U4") (pin "7") (pinfunction "NRST_7") (pintype "unspecified"))
    )
  )
)
